# POWER.net
KiCad netlist of a schematic drawn in Altium Designer
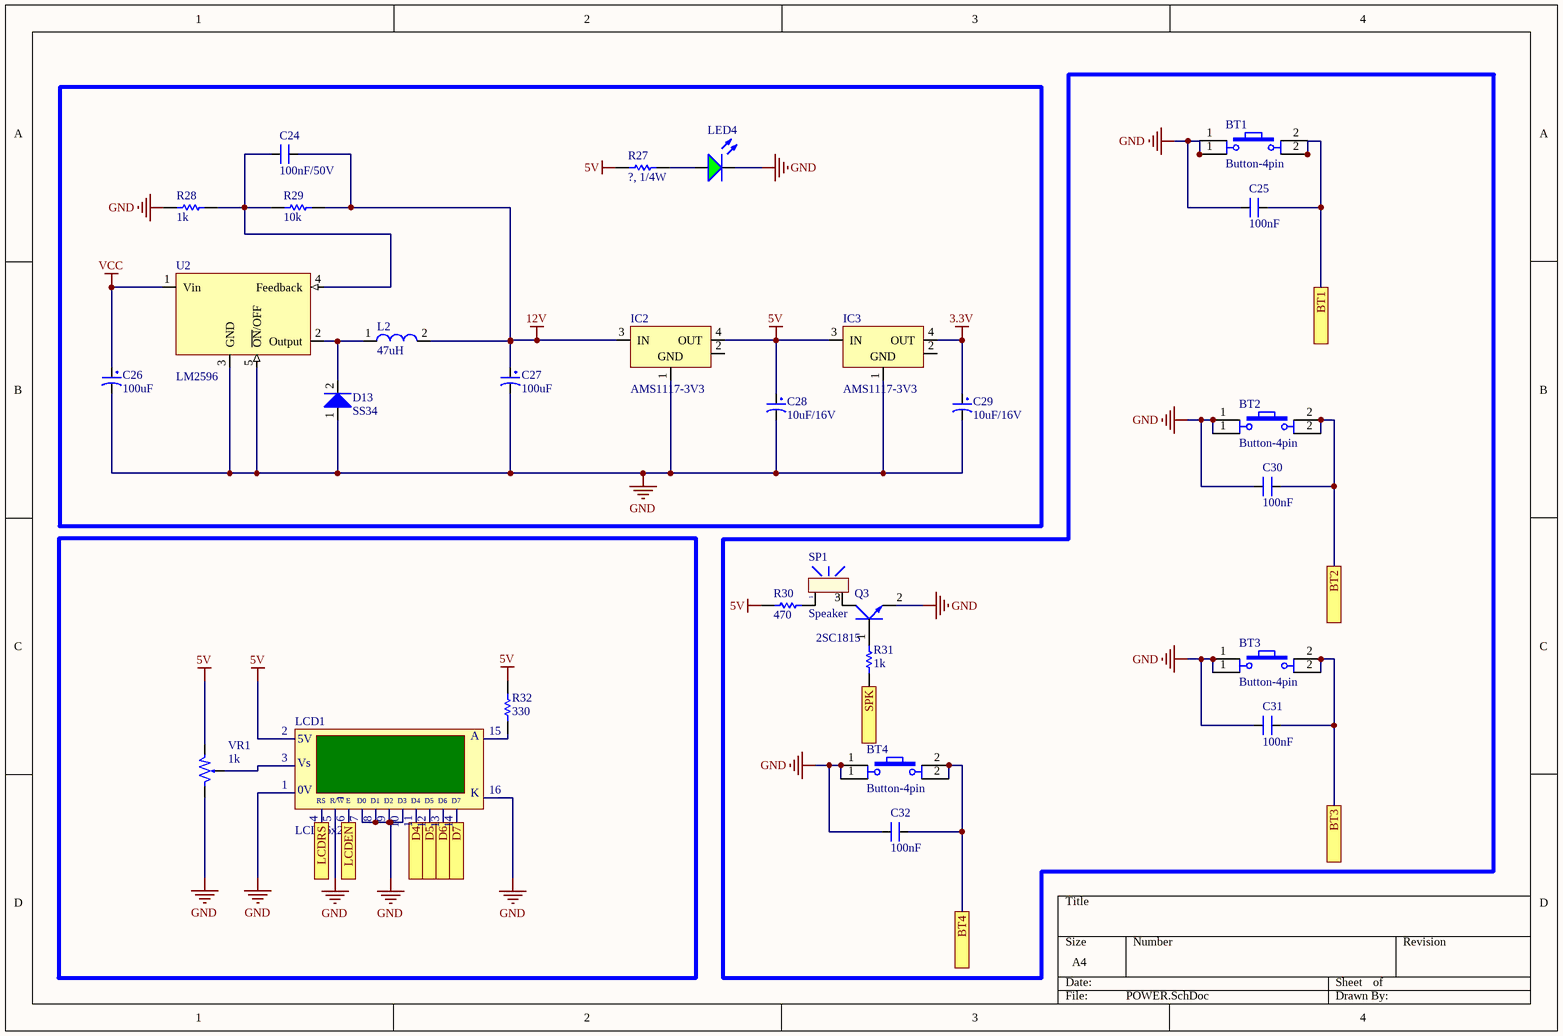
[diagram p0: POWER.SchDoc]

(export (version "E")
  (design (tool "Eeschema 10.0.6"))
  (components
    (comp (ref "BT1")
      (value "Button-4pin")
      (footprint "Button 12x12x7.3mm")
      (libsource (lib "Duc") (part "Button-4pin"))
    )
    (comp (ref "BT2")
      (value "Button-4pin")
      (footprint "Button 12x12x7.3mm")
      (libsource (lib "Duc") (part "Button-4pin"))
    )
    (comp (ref "BT3")
      (value "Button-4pin")
      (footprint "Button 12x12x7.3mm")
      (libsource (lib "Duc") (part "Button-4pin"))
    )
    (comp (ref "BT4")
      (value "Button-4pin")
      (footprint "Button 12x12x7.3mm")
      (libsource (lib "Duc") (part "Button-4pin"))
    )
    (comp (ref "C24")
      (value "100nF/50V")
      (footprint "RES 0603(1508)")
      (description "Ceramic Capacitor 100nF/50V (+-20% TH)/(+10%SMD)")
      (libsource (lib "Duc") (part "CAP_CER_100nF_50V_NPOL"))
    )
    (comp (ref "C25")
      (value "100nF")
      (footprint "CAP 0603(1508)")
      (description "Ceramic Capacitor 1nF/50V (+-20% TH)/(+10%SMD)")
      (libsource (lib "Duc") (part "CAP_CER_1nF_50V_NPOL"))
    )
    (comp (ref "C26")
      (value "100uF")
      (footprint "CAP_ALU_SIZED8")
      (description "Aluminum Capacitor 100uF size D")
      (libsource (lib "Duc") (part "CAP_ALU_100uF_35V_POL_SMD"))
    )
    (comp (ref "C27")
      (value "100uF")
      (footprint "CAP_ALU_SIZED8")
      (description "Aluminum Capacitor 100uF size D")
      (libsource (lib "Duc") (part "CAP_ALU_100uF_35V_POL_SMD"))
    )
    (comp (ref "C28")
      (value "10uF/16V")
      (footprint "CAP_TAN_1206(3216)")
      (description "Tantalum SMD capacitor 10uF(+-10%),TAJA106K010RNJ")
      (libsource (lib "Duc") (part "CAP_TANTA_10uF_16V_POL"))
    )
    (comp (ref "C29")
      (value "10uF/16V")
      (footprint "CAP_TAN_1206(3216)")
      (description "Tantalum SMD capacitor 10uF(+-10%),TAJA106K010RNJ")
      (libsource (lib "Duc") (part "CAP_TANTA_10uF_16V_POL"))
    )
    (comp (ref "C30")
      (value "100nF")
      (footprint "CAP 0603(1508)")
      (description "Ceramic Capacitor 1nF/50V (+-20% TH)/(+10%SMD)")
      (libsource (lib "Duc") (part "CAP_CER_1nF_50V_NPOL"))
    )
    (comp (ref "C31")
      (value "100nF")
      (footprint "CAP 0603(1508)")
      (description "Ceramic Capacitor 1nF/50V (+-20% TH)/(+10%SMD)")
      (libsource (lib "Duc") (part "CAP_CER_1nF_50V_NPOL"))
    )
    (comp (ref "C32")
      (value "100nF")
      (footprint "CAP 0603(1508)")
      (description "Ceramic Capacitor 1nF/50V (+-20% TH)/(+10%SMD)")
      (libsource (lib "Duc") (part "CAP_CER_1nF_50V_NPOL"))
    )
    (comp (ref "D13") (value "SS34") (footprint "SS34") (libsource (lib "Duc") (part "SS34")))
    (comp (ref "IC2")
      (value "AMS1117-3V3")
      (footprint "AMS1117")
      (description "Linear Voltage Regulator 3.3V 1A 15V Max SOT-223")
      (libsource (lib "Duc") (part "AMS1117-3V3"))
    )
    (comp (ref "IC3")
      (value "AMS1117-3V3")
      (footprint "AMS1117")
      (description "Linear Voltage Regulator 3.3V 1A 15V Max SOT-223")
      (libsource (lib "Duc") (part "AMS1117-3V3"))
    )
    (comp (ref "L2")
      (value "47uH")
      (footprint "Inductor SMD 48x48x28mm")
      (libsource (lib "Duc") (part "Inductor"))
    )
    (comp (ref "LCD1") (value "LCD16x2") (footprint "LCD16x2") (libsource (lib "Duc") (part "LCD16x2")))
    (comp (ref "LED4")
      (value "LED_GREEN")
      (footprint "LED0805GREEN")
      (description "LED Green")
      (libsource (lib "Duc") (part "LED_GREEN"))
    )
    (comp (ref "Q3")
      (value "2SC1815")
      (footprint "2SC1815-SMD")
      (description "NPN")
      (libsource (lib "Duc") (part "2SC1815"))
    )
    (comp (ref "R27")
      (value "?, 1/4W")
      (footprint "RES 0603(1508)")
      (description "Resistor through hole 1/4W")
      (libsource (lib "Duc") (part "Resistor 1/4W"))
    )
    (comp (ref "R28")
      (value "1k")
      (footprint "RES 0603(1508)")
      (description "Resistor through hole 1/4W")
      (libsource (lib "Duc") (part "Resistor 1/4W"))
    )
    (comp (ref "R29")
      (value "10k")
      (footprint "RES 0603(1508)")
      (description "Resistor through hole 1/4W")
      (libsource (lib "Duc") (part "Resistor 1/4W"))
    )
    (comp (ref "R30")
      (value "470")
      (footprint "RES 0603(1508)")
      (description "Resistor through hole 1/4W")
      (libsource (lib "Duc") (part "Resistor 1/4W"))
    )
    (comp (ref "R31")
      (value "1k")
      (footprint "RES 0603(1508)")
      (description "Resistor through hole 1/4W")
      (libsource (lib "Duc") (part "Resistor 1/4W"))
    )
    (comp (ref "R32")
      (value "330")
      (footprint "RES 0603(1508)")
      (description "Resistor through hole 1/4W")
      (libsource (lib "Duc") (part "Resistor 1/4W"))
    )
    (comp (ref "SP1")
      (value "Speaker")
      (footprint "Speaker")
      (description "Buzzer through hole (3V3/5V/12V)")
      (libsource (lib "Duc") (part "Speaker"))
    )
    (comp (ref "U2")
      (value "LM2596")
      (footprint "LM2596")
      (description "Step-Down Switching Regulator 5V 3.0 A 15 V Max")
      (libsource (lib "Duc") (part "LM2596"))
    )
    (comp (ref "VR1")
      (value "1k")
      (footprint "Trimmer 3262")
      (description "WH148")
      (libsource (lib "Duc") (part "Variable Resistor"))
    )
  )
  (nets
    (net (code "1") (name "/BT1") (class "Default")
      (node (ref "BT1") (pin "2") (pintype "passive"))
      (node (ref "C25") (pin "1") (pinfunction "1_1") (pintype "passive"))
    )
    (net (code "2") (name "/BT2") (class "Default")
      (node (ref "BT2") (pin "2") (pintype "passive"))
      (node (ref "C30") (pin "1") (pinfunction "1_1") (pintype "passive"))
    )
    (net (code "3") (name "/BT3") (class "Default")
      (node (ref "BT3") (pin "2") (pintype "passive"))
      (node (ref "C31") (pin "1") (pinfunction "1_1") (pintype "passive"))
    )
    (net (code "4") (name "/BT4") (class "Default")
      (node (ref "BT4") (pin "2") (pintype "passive"))
      (node (ref "C32") (pin "1") (pinfunction "1_1") (pintype "passive"))
    )
    (net (code "5") (name "/D4") (class "Default")
      (node (ref "LCD1") (pin "11") (pinfunction "11_11") (pintype "passive"))
    )
    (net (code "6") (name "/D5") (class "Default")
      (node (ref "LCD1") (pin "12") (pinfunction "12_12") (pintype "passive"))
    )
    (net (code "7") (name "/D6") (class "Default")
      (node (ref "LCD1") (pin "13") (pinfunction "13_13") (pintype "passive"))
    )
    (net (code "8") (name "/D7") (class "Default")
      (node (ref "LCD1") (pin "14") (pinfunction "14_14") (pintype "passive"))
    )
    (net (code "9") (name "/LCDEN") (class "Default")
      (node (ref "LCD1") (pin "6") (pinfunction "6_6") (pintype "passive"))
    )
    (net (code "10") (name "/LCDRS") (class "Default")
      (node (ref "LCD1") (pin "4") (pinfunction "4_4") (pintype "passive"))
    )
    (net (code "11") (name "/SPK") (class "Default")
      (node (ref "R31") (pin "1") (pinfunction "1_1") (pintype "passive"))
    )
    (net (code "12") (name "3.3V") (class "Default")
      (node (ref "C29") (pin "1") (pinfunction "1_1") (pintype "passive"))
      (node (ref "IC3") (pin "4") (pinfunction "OUT_4") (pintype "power_in"))
    )
    (net (code "13") (name "5V") (class "Default")
      (node (ref "C28") (pin "1") (pinfunction "1_1") (pintype "passive"))
      (node (ref "IC2") (pin "4") (pinfunction "OUT_4") (pintype "power_in"))
      (node (ref "IC3") (pin "3") (pinfunction "IN_3") (pintype "power_in"))
      (node (ref "LCD1") (pin "2") (pinfunction "2_2") (pintype "passive"))
      (node (ref "R27") (pin "2") (pinfunction "2_2") (pintype "passive"))
      (node (ref "R30") (pin "1") (pinfunction "1_1") (pintype "passive"))
      (node (ref "R32") (pin "1") (pinfunction "1_1") (pintype "passive"))
      (node (ref "VR1") (pin "1") (pinfunction "1_1") (pintype "passive"))
    )
    (net (code "14") (name "12V") (class "Default")
      (node (ref "C24") (pin "2") (pinfunction "2_2") (pintype "passive"))
      (node (ref "C27") (pin "1") (pinfunction "1_1") (pintype "passive"))
      (node (ref "IC2") (pin "3") (pinfunction "IN_3") (pintype "power_in"))
      (node (ref "L2") (pin "2") (pinfunction "2_2") (pintype "passive"))
      (node (ref "R29") (pin "1") (pinfunction "1_1") (pintype "passive"))
    )
    (net (code "15") (name "GND") (class "Default")
      (node (ref "BT1") (pin "1") (pintype "passive"))
      (node (ref "BT2") (pin "1") (pintype "passive"))
      (node (ref "BT3") (pin "1") (pintype "passive"))
      (node (ref "BT4") (pin "1") (pintype "passive"))
      (node (ref "C25") (pin "2") (pinfunction "2_2") (pintype "passive"))
      (node (ref "C26") (pin "2") (pinfunction "2_2") (pintype "passive"))
      (node (ref "C27") (pin "2") (pinfunction "2_2") (pintype "passive"))
      (node (ref "C28") (pin "2") (pinfunction "2_2") (pintype "passive"))
      (node (ref "C29") (pin "2") (pinfunction "2_2") (pintype "passive"))
      (node (ref "C30") (pin "2") (pinfunction "2_2") (pintype "passive"))
      (node (ref "C31") (pin "2") (pinfunction "2_2") (pintype "passive"))
      (node (ref "C32") (pin "2") (pinfunction "2_2") (pintype "passive"))
      (node (ref "D13") (pin "1") (pinfunction "A_1") (pintype "passive"))
      (node (ref "IC2") (pin "1") (pinfunction "GND_1") (pintype "power_in"))
      (node (ref "IC3") (pin "1") (pinfunction "GND_1") (pintype "power_in"))
      (node (ref "LCD1") (pin "1") (pinfunction "1_1") (pintype "passive"))
      (node (ref "LCD1") (pin "10") (pinfunction "10_10") (pintype "passive"))
      (node (ref "LCD1") (pin "16") (pinfunction "16_16") (pintype "passive"))
      (node (ref "LCD1") (pin "5") (pinfunction "5_5") (pintype "passive"))
      (node (ref "LCD1") (pin "7") (pinfunction "7_7") (pintype "passive"))
      (node (ref "LCD1") (pin "8") (pinfunction "8_8") (pintype "passive"))
      (node (ref "LCD1") (pin "9") (pinfunction "9_9") (pintype "passive"))
      (node (ref "LED4") (pin "2") (pinfunction "K_2") (pintype "passive"))
      (node (ref "Q3") (pin "2") (pinfunction "E_2") (pintype "passive"))
      (node (ref "R28") (pin "2") (pinfunction "2_2") (pintype "passive"))
      (node (ref "U2") (pin "3") (pinfunction "GND_3") (pintype "power_in"))
      (node (ref "U2") (pin "5") (pinfunction "~{ON}/OFF_5") (pintype "input"))
      (node (ref "VR1") (pin "3") (pinfunction "3_3") (pintype "passive"))
    )
    (net (code "16") (name "Net-(D13-K)") (class "Default")
      (node (ref "D13") (pin "2") (pinfunction "K_2") (pintype "passive"))
      (node (ref "L2") (pin "1") (pinfunction "1_1") (pintype "passive"))
      (node (ref "U2") (pin "2") (pinfunction "Output_2") (pintype "power_in"))
    )
    (net (code "17") (name "Net-(LCD1-Pad3)") (class "Default")
      (node (ref "LCD1") (pin "3") (pinfunction "3_3") (pintype "passive"))
      (node (ref "VR1") (pin "2") (pinfunction "2_2") (pintype "passive"))
    )
    (net (code "18") (name "Net-(LCD1-VCC)") (class "Default")
      (node (ref "LCD1") (pin "15") (pinfunction "VCC_15") (pintype "passive"))
      (node (ref "R32") (pin "2") (pinfunction "2_2") (pintype "passive"))
    )
    (net (code "19") (name "Net-(LED4-A)") (class "Default")
      (node (ref "LED4") (pin "1") (pinfunction "A_1") (pintype "passive"))
      (node (ref "R27") (pin "1") (pinfunction "1_1") (pintype "passive"))
    )
    (net (code "20") (name "Net-(Q3-B)") (class "Default")
      (node (ref "Q3") (pin "1") (pinfunction "B_1") (pintype "passive"))
      (node (ref "R31") (pin "2") (pinfunction "2_2") (pintype "passive"))
    )
    (net (code "21") (name "Net-(Q3-C)") (class "Default")
      (node (ref "Q3") (pin "3") (pinfunction "C_3") (pintype "passive"))
      (node (ref "SP1") (pin "2") (pinfunction "2_2") (pintype "passive"))
    )
    (net (code "22") (name "Net-(R30-Pad2)") (class "Default")
      (node (ref "R30") (pin "2") (pinfunction "2_2") (pintype "passive"))
      (node (ref "SP1") (pin "1") (pinfunction "1_1") (pintype "passive"))
    )
    (net (code "23") (name "Net-(U2-Feedback)") (class "Default")
      (node (ref "C24") (pin "1") (pinfunction "1_1") (pintype "passive"))
      (node (ref "R28") (pin "1") (pinfunction "1_1") (pintype "passive"))
      (node (ref "R29") (pin "2") (pinfunction "2_2") (pintype "passive"))
      (node (ref "U2") (pin "4") (pinfunction "Feedback_4") (pintype "input"))
    )
    (net (code "24") (name "VCC") (class "Default")
      (node (ref "C26") (pin "1") (pinfunction "1_1") (pintype "passive"))
      (node (ref "U2") (pin "1") (pinfunction "Vin_1") (pintype "power_in"))
    )
    (net (code "25") (name "unconnected-(BT1-Pad1)") (class "Default")
      (node (ref "BT1") (pin "1") (pintype "passive"))
    )
    (net (code "26") (name "unconnected-(BT1-Pad2)") (class "Default")
      (node (ref "BT1") (pin "2") (pintype "passive"))
    )
    (net (code "27") (name "unconnected-(IC2-OUT-Pad2)") (class "Default")
      (node (ref "IC2") (pin "2") (pinfunction "OUT_2") (pintype "power_in"))
    )
    (net (code "28") (name "unconnected-(IC3-OUT-Pad2)") (class "Default")
      (node (ref "IC3") (pin "2") (pinfunction "OUT_2") (pintype "power_in"))
    )
  )
)
